# shieldMegaEstacionTT.net
KiCad netlist of a schematic drawn in Altium Designer
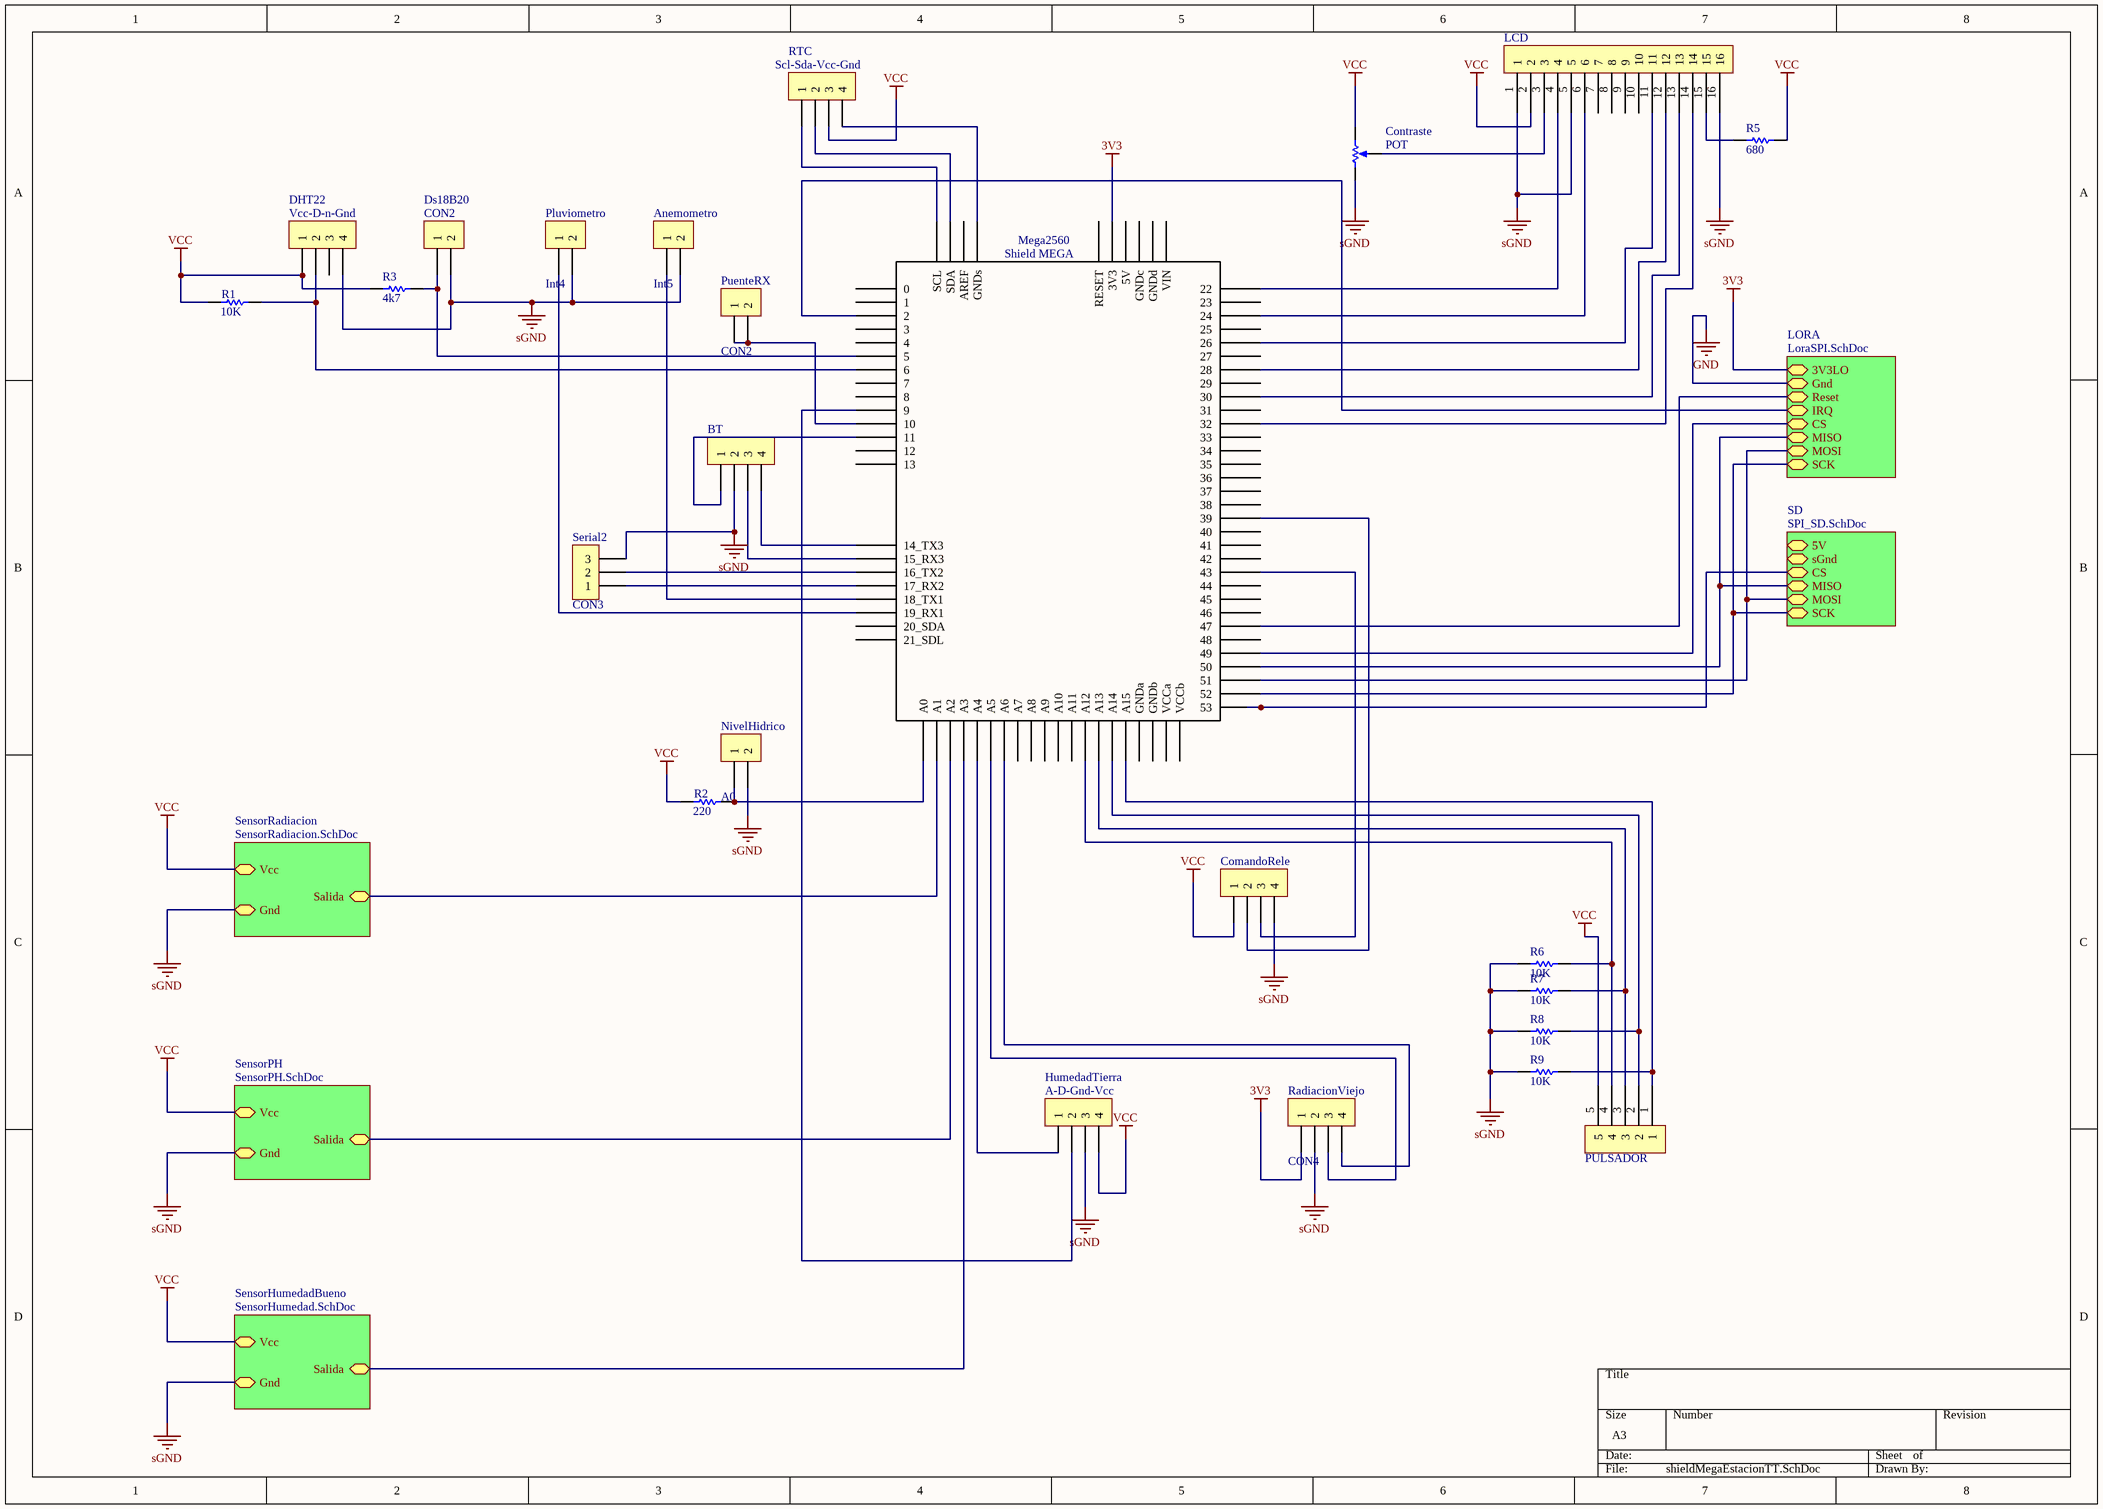
[diagram p0: shieldMegaEstacionTT.SchDoc]

(export (version "E")
  (design (tool "Eeschema 10.0.6"))
  (components
    (comp (ref "Anemometro")
      (value "Int5")
      (footprint "BORNERA2 - T")
      (description "Conector 2")
      (libsource (lib "IDTILab") (part "CON2"))
    )
    (comp (ref "BT")
      (value "CON4")
      (footprint "CON4")
      (description "Conector 4")
      (libsource (lib "DIE-SA Ingenieria") (part "CON4"))
    )
    (comp (ref "ComandoRele")
      (value "CON4")
      (footprint "CON4")
      (description "Conector 4")
      (libsource (lib "DIE-SA Ingenieria") (part "CON4"))
    )
    (comp (ref "Contraste")
      (value "POT")
      (footprint "PRESET2")
      (description "Potenciometro - Preset")
      (libsource (lib "DIE-SA Ingenieria") (part "POT"))
    )
    (comp (ref "DHT22")
      (value "Vcc-D-n-Gnd")
      (footprint "BORNERA4")
      (description "Conector 4")
      (libsource (lib "DIE-SA Ingenieria") (part "CON4"))
    )
    (comp (ref "Ds18B20")
      (value "CON2")
      (footprint "BORNERA2 - T")
      (description "Conector 2")
      (libsource (lib "IDTILab") (part "CON2"))
    )
    (comp (ref "HumedadTierra")
      (value "A-D-Gnd-Vcc")
      (footprint "CON4")
      (description "Conector 4")
      (libsource (lib "DIE-SA Ingenieria") (part "CON4"))
    )
    (comp (ref "LCD")
      (value "CON16")
      (footprint "CON2X8")
      (description "Conector 16")
      (libsource (lib "DIE-SA Ingenieria") (part "CON16"))
    )
    (comp (ref "Mega2560")
      (value "Shield MEGA")
      (footprint "Shield Mega")
      (libsource (lib "IDTILab") (part "Shield MEGA"))
    )
    (comp (ref "NivelHidrico")
      (value "A0")
      (footprint "BORNERA2 - T")
      (description "Conector 2")
      (libsource (lib "IDTILab") (part "CON2"))
    )
    (comp (ref "Pluviometro")
      (value "Int4")
      (footprint "BORNERA2 - T")
      (description "Conector 2")
      (libsource (lib "DIE-SA Ingenieria") (part "CON2"))
    )
    (comp (ref "PuenteRX")
      (value "CON2")
      (footprint "CON2")
      (description "Conector 2")
      (libsource (lib "IDTILab") (part "CON2"))
    )
    (comp (ref "PULSADOR")
      (value "CON5")
      (footprint "CON5")
      (description "Conector 5")
      (libsource (lib "DIE-SA Ingenieria") (part "CON5"))
    )
    (comp (ref "R1")
      (value "10K")
      (footprint "DIE-SA Ingenieria:RES300")
      (description "Resistencia")
      (libsource (lib "DIE-SA Ingenieria") (part "RES"))
    )
    (comp (ref "R2")
      (value "220")
      (footprint "DIE-SA Ingenieria:RES300")
      (description "Resistencia")
      (libsource (lib "DIE-SA Ingenieria") (part "RES"))
    )
    (comp (ref "R3")
      (value "4k7")
      (footprint "RES300")
      (description "Resistencia")
      (libsource (lib "DIE-SA Ingenieria") (part "RES"))
    )
    (comp (ref "R5")
      (value "680")
      (footprint "RES300")
      (description "Resistencia")
      (libsource (lib "DIE-SA Ingenieria") (part "RES"))
    )
    (comp (ref "R6")
      (value "10K")
      (footprint "RES300")
      (description "Resistencia")
      (libsource (lib "DIE-SA Ingenieria") (part "RES"))
    )
    (comp (ref "R7")
      (value "10K")
      (footprint "RES300")
      (description "Resistencia")
      (libsource (lib "DIE-SA Ingenieria") (part "RES"))
    )
    (comp (ref "R8")
      (value "10K")
      (footprint "RES300")
      (description "Resistencia")
      (libsource (lib "DIE-SA Ingenieria") (part "RES"))
    )
    (comp (ref "R9")
      (value "10K")
      (footprint "RES300")
      (description "Resistencia")
      (libsource (lib "DIE-SA Ingenieria") (part "RES"))
    )
    (comp (ref "RadiacionViejo")
      (value "CON4")
      (footprint "BORNERA4 - T")
      (description "Conector 4")
      (libsource (lib "DIE-SA Ingenieria") (part "CON4"))
    )
    (comp (ref "RTC")
      (value "Scl-Sda-Vcc-Gnd")
      (footprint "CON4")
      (description "Conector 4")
      (libsource (lib "DIE-SA Ingenieria") (part "CON4"))
    )
    (comp (ref "Serial2")
      (value "CON3")
      (footprint "CON3")
      (description "Conector 3")
      (libsource (lib "IDTILab") (part "CON3"))
    )
  )
  (nets
    (net (code "2") (name "/CS") (class "Default")
      (node (ref "Mega2560") (pin "49") (pinfunction "49_49") (pintype "passive"))
    )
    (net (code "3") (name "/CS_1") (class "Default")
      (node (ref "Mega2560") (pin "53") (pinfunction "53_53") (pintype "passive"))
    )
    (net (code "4") (name "/IRQ") (class "Default")
      (node (ref "Mega2560") (pin "2") (pinfunction "2_2") (pintype "passive"))
    )
    (net (code "5") (name "/MISO") (class "Default")
      (node (ref "Mega2560") (pin "50") (pinfunction "50_50") (pintype "passive"))
    )
    (net (code "6") (name "/MOSI") (class "Default")
      (node (ref "Mega2560") (pin "51") (pinfunction "51_51") (pintype "passive"))
    )
    (net (code "7") (name "/Reset") (class "Default")
      (node (ref "Mega2560") (pin "47") (pinfunction "47_47") (pintype "passive"))
    )
    (net (code "8") (name "/SCK") (class "Default")
      (node (ref "Mega2560") (pin "52") (pinfunction "52_52") (pintype "passive"))
    )
    (net (code "9") (name "/Salida") (class "Default")
      (node (ref "Mega2560") (pin "A3") (pinfunction "A3_A3") (pintype "passive"))
    )
    (net (code "10") (name "/Salida_1") (class "Default")
      (node (ref "Mega2560") (pin "A1") (pinfunction "A1_A1") (pintype "passive"))
    )
    (net (code "11") (name "/Salida_2") (class "Default")
      (node (ref "Mega2560") (pin "A2") (pinfunction "A2_A2") (pintype "passive"))
    )
    (net (code "13") (name "3V3") (class "Default")
      (node (ref "Mega2560") (pin "3V3") (pinfunction "3V3_3V3") (pintype "passive"))
      (node (ref "RadiacionViejo") (pin "1") (pinfunction "1_1") (pintype "passive"))
    )
    (net (code "15") (name "Net-(BT-Pad1)") (class "Default")
      (node (ref "BT") (pin "1") (pinfunction "1_1") (pintype "passive"))
      (node (ref "Mega2560") (pin "11") (pinfunction "11_11") (pintype "passive"))
    )
    (net (code "16") (name "Net-(ComandoRele-Pad2)") (class "Default")
      (node (ref "ComandoRele") (pin "2") (pinfunction "2_2") (pintype "passive"))
      (node (ref "Mega2560") (pin "39") (pinfunction "39_39") (pintype "passive"))
    )
    (net (code "17") (name "Net-(ComandoRele-Pad3)") (class "Default")
      (node (ref "ComandoRele") (pin "3") (pinfunction "3_3") (pintype "passive"))
      (node (ref "Mega2560") (pin "43") (pinfunction "43_43") (pintype "passive"))
    )
    (net (code "18") (name "Net-(Contraste-Pad3)") (class "Default")
      (node (ref "Contraste") (pin "3") (pinfunction "3_3") (pintype "passive"))
      (node (ref "LCD") (pin "3") (pinfunction "3_3") (pintype "passive"))
    )
    (net (code "19") (name "Net-(DHT22-Pad2)") (class "Default")
      (node (ref "DHT22") (pin "2") (pinfunction "2_2") (pintype "passive"))
      (node (ref "Mega2560") (pin "6") (pinfunction "6_6") (pintype "passive"))
      (node (ref "R1") (pin "2") (pinfunction "2_2") (pintype "passive"))
    )
    (net (code "20") (name "Net-(Ds18B20-Pad1)") (class "Default")
      (node (ref "Ds18B20") (pin "1") (pinfunction "1_1") (pintype "passive"))
      (node (ref "Mega2560") (pin "5") (pinfunction "5_5") (pintype "passive"))
      (node (ref "R3") (pin "2") (pinfunction "2_2") (pintype "passive"))
    )
    (net (code "21") (name "Net-(HumedadTierra-Pad1)") (class "Default")
      (node (ref "HumedadTierra") (pin "1") (pinfunction "1_1") (pintype "passive"))
      (node (ref "Mega2560") (pin "A4") (pinfunction "A4_A4") (pintype "passive"))
    )
    (net (code "22") (name "Net-(HumedadTierra-Pad2)") (class "Default")
      (node (ref "HumedadTierra") (pin "2") (pinfunction "2_2") (pintype "passive"))
      (node (ref "Mega2560") (pin "9") (pinfunction "9_9") (pintype "passive"))
    )
    (net (code "23") (name "Net-(LCD-Pad4)") (class "Default")
      (node (ref "LCD") (pin "4") (pinfunction "4_4") (pintype "passive"))
      (node (ref "Mega2560") (pin "22") (pinfunction "22_22") (pintype "passive"))
    )
    (net (code "24") (name "Net-(LCD-Pad6)") (class "Default")
      (node (ref "LCD") (pin "6") (pinfunction "6_6") (pintype "passive"))
      (node (ref "Mega2560") (pin "24") (pinfunction "24_24") (pintype "passive"))
    )
    (net (code "25") (name "Net-(LCD-Pad11)") (class "Default")
      (node (ref "LCD") (pin "11") (pinfunction "11_11") (pintype "passive"))
      (node (ref "Mega2560") (pin "26") (pinfunction "26_26") (pintype "passive"))
    )
    (net (code "26") (name "Net-(LCD-Pad12)") (class "Default")
      (node (ref "LCD") (pin "12") (pinfunction "12_12") (pintype "passive"))
      (node (ref "Mega2560") (pin "28") (pinfunction "28_28") (pintype "passive"))
    )
    (net (code "27") (name "Net-(LCD-Pad13)") (class "Default")
      (node (ref "LCD") (pin "13") (pinfunction "13_13") (pintype "passive"))
      (node (ref "Mega2560") (pin "30") (pinfunction "30_30") (pintype "passive"))
    )
    (net (code "28") (name "Net-(LCD-Pad14)") (class "Default")
      (node (ref "LCD") (pin "14") (pinfunction "14_14") (pintype "passive"))
      (node (ref "Mega2560") (pin "32") (pinfunction "32_32") (pintype "passive"))
    )
    (net (code "29") (name "Net-(LCD-Pad15)") (class "Default")
      (node (ref "LCD") (pin "15") (pinfunction "15_15") (pintype "passive"))
      (node (ref "R5") (pin "2") (pinfunction "2_2") (pintype "passive"))
    )
    (net (code "30") (name "Net-(Mega2560-14_TX3)") (class "Default")
      (node (ref "BT") (pin "4") (pinfunction "4_4") (pintype "passive"))
      (node (ref "Mega2560") (pin "14") (pinfunction "14_TX3_14") (pintype "passive"))
    )
    (net (code "31") (name "Net-(Mega2560-15_RX3)") (class "Default")
      (node (ref "BT") (pin "3") (pinfunction "3_3") (pintype "passive"))
      (node (ref "Mega2560") (pin "15") (pinfunction "15_RX3_15") (pintype "passive"))
    )
    (net (code "32") (name "Net-(Mega2560-16_TX2)") (class "Default")
      (node (ref "Mega2560") (pin "16") (pinfunction "16_TX2_16") (pintype "passive"))
      (node (ref "Serial2") (pin "2") (pinfunction "2_2") (pintype "passive"))
    )
    (net (code "33") (name "Net-(Mega2560-17_RX2)") (class "Default")
      (node (ref "Mega2560") (pin "17") (pinfunction "17_RX2_17") (pintype "passive"))
      (node (ref "Serial2") (pin "1") (pinfunction "1_1") (pintype "passive"))
    )
    (net (code "34") (name "Net-(Mega2560-18_TX1)") (class "Default")
      (node (ref "Anemometro") (pin "1") (pinfunction "1_1") (pintype "passive"))
      (node (ref "Mega2560") (pin "18") (pinfunction "18_TX1_18") (pintype "passive"))
    )
    (net (code "35") (name "Net-(Mega2560-19_RX1)") (class "Default")
      (node (ref "Mega2560") (pin "19") (pinfunction "19_RX1_19") (pintype "passive"))
      (node (ref "Pluviometro") (pin "1") (pinfunction "1_1") (pintype "passive"))
    )
    (net (code "36") (name "Net-(Mega2560-Pad10)") (class "Default")
      (node (ref "Mega2560") (pin "10") (pinfunction "10_10") (pintype "passive"))
      (node (ref "PuenteRX") (pin "1") (pinfunction "1_1") (pintype "passive"))
      (node (ref "PuenteRX") (pin "2") (pinfunction "2_2") (pintype "passive"))
    )
    (net (code "37") (name "Net-(Mega2560-PadA0)") (class "Default")
      (node (ref "Mega2560") (pin "A0") (pinfunction "A0_A0") (pintype "passive"))
      (node (ref "NivelHidrico") (pin "1") (pinfunction "1_1") (pintype "passive"))
      (node (ref "R2") (pin "2") (pinfunction "2_2") (pintype "passive"))
    )
    (net (code "38") (name "Net-(Mega2560-PadA5)") (class "Default")
      (node (ref "Mega2560") (pin "A5") (pinfunction "A5_A5") (pintype "passive"))
      (node (ref "RadiacionViejo") (pin "3") (pinfunction "3_3") (pintype "passive"))
    )
    (net (code "39") (name "Net-(Mega2560-PadA6)") (class "Default")
      (node (ref "Mega2560") (pin "A6") (pinfunction "A6_A6") (pintype "passive"))
      (node (ref "RadiacionViejo") (pin "4") (pinfunction "4_4") (pintype "passive"))
    )
    (net (code "40") (name "Net-(Mega2560-PadA12)") (class "Default")
      (node (ref "Mega2560") (pin "A12") (pinfunction "A12_A12") (pintype "passive"))
      (node (ref "PULSADOR") (pin "4") (pinfunction "4_4") (pintype "passive"))
      (node (ref "R6") (pin "2") (pinfunction "2_2") (pintype "passive"))
    )
    (net (code "41") (name "Net-(Mega2560-PadA13)") (class "Default")
      (node (ref "Mega2560") (pin "A13") (pinfunction "A13_A13") (pintype "passive"))
      (node (ref "PULSADOR") (pin "3") (pinfunction "3_3") (pintype "passive"))
      (node (ref "R7") (pin "2") (pinfunction "2_2") (pintype "passive"))
    )
    (net (code "42") (name "Net-(Mega2560-PadA14)") (class "Default")
      (node (ref "Mega2560") (pin "A14") (pinfunction "A14_A14") (pintype "passive"))
      (node (ref "PULSADOR") (pin "2") (pinfunction "2_2") (pintype "passive"))
      (node (ref "R8") (pin "2") (pinfunction "2_2") (pintype "passive"))
    )
    (net (code "43") (name "Net-(Mega2560-PadA15)") (class "Default")
      (node (ref "Mega2560") (pin "A15") (pinfunction "A15_A15") (pintype "passive"))
      (node (ref "PULSADOR") (pin "1") (pinfunction "1_1") (pintype "passive"))
      (node (ref "R9") (pin "2") (pinfunction "2_2") (pintype "passive"))
    )
    (net (code "44") (name "Net-(Mega2560-PadGNDs)") (class "Default")
      (node (ref "Mega2560") (pin "GNDs") (pinfunction "GNDs_GNDs") (pintype "passive"))
      (node (ref "RTC") (pin "4") (pinfunction "4_4") (pintype "passive"))
    )
    (net (code "45") (name "Net-(Mega2560-PadSCL)") (class "Default")
      (node (ref "Mega2560") (pin "SCL") (pinfunction "SCL_SCL") (pintype "passive"))
      (node (ref "RTC") (pin "1") (pinfunction "1_1") (pintype "passive"))
    )
    (net (code "46") (name "Net-(Mega2560-PadSDA)") (class "Default")
      (node (ref "Mega2560") (pin "SDA") (pinfunction "SDA_SDA") (pintype "passive"))
      (node (ref "RTC") (pin "2") (pinfunction "2_2") (pintype "passive"))
    )
    (net (code "47") (name "VCC") (class "Default")
      (node (ref "ComandoRele") (pin "1") (pinfunction "1_1") (pintype "passive"))
      (node (ref "Contraste") (pin "1") (pinfunction "1_1") (pintype "passive"))
      (node (ref "DHT22") (pin "1") (pinfunction "1_1") (pintype "passive"))
      (node (ref "HumedadTierra") (pin "4") (pinfunction "4_4") (pintype "passive"))
      (node (ref "LCD") (pin "2") (pinfunction "2_2") (pintype "passive"))
      (node (ref "PULSADOR") (pin "5") (pinfunction "5_5") (pintype "passive"))
      (node (ref "R1") (pin "1") (pinfunction "1_1") (pintype "passive"))
      (node (ref "R2") (pin "1") (pinfunction "1_1") (pintype "passive"))
      (node (ref "R3") (pin "1") (pinfunction "1_1") (pintype "passive"))
      (node (ref "R5") (pin "1") (pinfunction "1_1") (pintype "passive"))
      (node (ref "RTC") (pin "3") (pinfunction "3_3") (pintype "passive"))
    )
    (net (code "48") (name "sGND") (class "Default")
      (node (ref "Anemometro") (pin "2") (pinfunction "2_2") (pintype "passive"))
      (node (ref "BT") (pin "2") (pinfunction "2_2") (pintype "passive"))
      (node (ref "ComandoRele") (pin "4") (pinfunction "4_4") (pintype "passive"))
      (node (ref "Contraste") (pin "2") (pinfunction "2_2") (pintype "passive"))
      (node (ref "DHT22") (pin "4") (pinfunction "4_4") (pintype "passive"))
      (node (ref "Ds18B20") (pin "2") (pinfunction "2_2") (pintype "passive"))
      (node (ref "HumedadTierra") (pin "3") (pinfunction "3_3") (pintype "passive"))
      (node (ref "LCD") (pin "1") (pinfunction "1_1") (pintype "passive"))
      (node (ref "LCD") (pin "16") (pinfunction "16_16") (pintype "passive"))
      (node (ref "LCD") (pin "5") (pinfunction "5_5") (pintype "passive"))
      (node (ref "NivelHidrico") (pin "2") (pinfunction "2_2") (pintype "passive"))
      (node (ref "Pluviometro") (pin "2") (pinfunction "2_2") (pintype "passive"))
      (node (ref "R6") (pin "1") (pinfunction "1_1") (pintype "passive"))
      (node (ref "R7") (pin "1") (pinfunction "1_1") (pintype "passive"))
      (node (ref "R8") (pin "1") (pinfunction "1_1") (pintype "passive"))
      (node (ref "R9") (pin "1") (pinfunction "1_1") (pintype "passive"))
      (node (ref "RadiacionViejo") (pin "2") (pinfunction "2_2") (pintype "passive"))
      (node (ref "Serial2") (pin "3") (pinfunction "3_3") (pintype "passive"))
    )
    (net (code "49") (name "unconnected-(DHT22-Pad3)") (class "Default")
      (node (ref "DHT22") (pin "3") (pinfunction "3_3") (pintype "passive"))
    )
    (net (code "50") (name "unconnected-(LCD-Pad7)") (class "Default")
      (node (ref "LCD") (pin "7") (pinfunction "7_7") (pintype "passive"))
    )
    (net (code "51") (name "unconnected-(LCD-Pad8)") (class "Default")
      (node (ref "LCD") (pin "8") (pinfunction "8_8") (pintype "passive"))
    )
    (net (code "52") (name "unconnected-(LCD-Pad9)") (class "Default")
      (node (ref "LCD") (pin "9") (pinfunction "9_9") (pintype "passive"))
    )
    (net (code "53") (name "unconnected-(LCD-Pad10)") (class "Default")
      (node (ref "LCD") (pin "10") (pinfunction "10_10") (pintype "passive"))
    )
    (net (code "54") (name "unconnected-(Mega2560-20_SDA-Pad20)") (class "Default")
      (node (ref "Mega2560") (pin "20") (pinfunction "20_SDA_20") (pintype "passive"))
    )
    (net (code "55") (name "unconnected-(Mega2560-21_SDL-Pad21)") (class "Default")
      (node (ref "Mega2560") (pin "21") (pinfunction "21_SDL_21") (pintype "passive"))
    )
    (net (code "56") (name "unconnected-(Mega2560-Pad0)") (class "Default")
      (node (ref "Mega2560") (pin "0") (pinfunction "0_0") (pintype "passive"))
    )
    (net (code "57") (name "unconnected-(Mega2560-Pad1)") (class "Default")
      (node (ref "Mega2560") (pin "1") (pinfunction "1_1") (pintype "passive"))
    )
    (net (code "58") (name "unconnected-(Mega2560-Pad3)") (class "Default")
      (node (ref "Mega2560") (pin "3") (pinfunction "3_3") (pintype "passive"))
    )
    (net (code "59") (name "unconnected-(Mega2560-Pad4)") (class "Default")
      (node (ref "Mega2560") (pin "4") (pinfunction "4_4") (pintype "passive"))
    )
    (net (code "60") (name "unconnected-(Mega2560-Pad5V)") (class "Default")
      (node (ref "Mega2560") (pin "5V") (pinfunction "5V_5V") (pintype "passive"))
    )
    (net (code "61") (name "unconnected-(Mega2560-Pad7)") (class "Default")
      (node (ref "Mega2560") (pin "7") (pinfunction "7_7") (pintype "passive"))
    )
    (net (code "62") (name "unconnected-(Mega2560-Pad8)") (class "Default")
      (node (ref "Mega2560") (pin "8") (pinfunction "8_8") (pintype "passive"))
    )
    (net (code "63") (name "unconnected-(Mega2560-Pad12)") (class "Default")
      (node (ref "Mega2560") (pin "12") (pinfunction "12_12") (pintype "passive"))
    )
    (net (code "64") (name "unconnected-(Mega2560-Pad13)") (class "Default")
      (node (ref "Mega2560") (pin "13") (pinfunction "13_13") (pintype "passive"))
    )
    (net (code "65") (name "unconnected-(Mega2560-Pad23)") (class "Default")
      (node (ref "Mega2560") (pin "23") (pinfunction "23_23") (pintype "passive"))
    )
    (net (code "66") (name "unconnected-(Mega2560-Pad25)") (class "Default")
      (node (ref "Mega2560") (pin "25") (pinfunction "25_25") (pintype "passive"))
    )
    (net (code "67") (name "unconnected-(Mega2560-Pad27)") (class "Default")
      (node (ref "Mega2560") (pin "27") (pinfunction "27_27") (pintype "passive"))
    )
    (net (code "68") (name "unconnected-(Mega2560-Pad29)") (class "Default")
      (node (ref "Mega2560") (pin "29") (pinfunction "29_29") (pintype "passive"))
    )
    (net (code "69") (name "unconnected-(Mega2560-Pad31)") (class "Default")
      (node (ref "Mega2560") (pin "31") (pinfunction "31_31") (pintype "passive"))
    )
    (net (code "70") (name "unconnected-(Mega2560-Pad33)") (class "Default")
      (node (ref "Mega2560") (pin "33") (pinfunction "33_33") (pintype "passive"))
    )
    (net (code "71") (name "unconnected-(Mega2560-Pad34)") (class "Default")
      (node (ref "Mega2560") (pin "34") (pinfunction "34_34") (pintype "passive"))
    )
    (net (code "72") (name "unconnected-(Mega2560-Pad35)") (class "Default")
      (node (ref "Mega2560") (pin "35") (pinfunction "35_35") (pintype "passive"))
    )
    (net (code "73") (name "unconnected-(Mega2560-Pad36)") (class "Default")
      (node (ref "Mega2560") (pin "36") (pinfunction "36_36") (pintype "passive"))
    )
    (net (code "74") (name "unconnected-(Mega2560-Pad37)") (class "Default")
      (node (ref "Mega2560") (pin "37") (pinfunction "37_37") (pintype "passive"))
    )
    (net (code "75") (name "unconnected-(Mega2560-Pad38)") (class "Default")
      (node (ref "Mega2560") (pin "38") (pinfunction "38_38") (pintype "passive"))
    )
    (net (code "76") (name "unconnected-(Mega2560-Pad40)") (class "Default")
      (node (ref "Mega2560") (pin "40") (pinfunction "40_40") (pintype "passive"))
    )
    (net (code "77") (name "unconnected-(Mega2560-Pad41)") (class "Default")
      (node (ref "Mega2560") (pin "41") (pinfunction "41_41") (pintype "passive"))
    )
    (net (code "78") (name "unconnected-(Mega2560-Pad42)") (class "Default")
      (node (ref "Mega2560") (pin "42") (pinfunction "42_42") (pintype "passive"))
    )
    (net (code "79") (name "unconnected-(Mega2560-Pad44)") (class "Default")
      (node (ref "Mega2560") (pin "44") (pinfunction "44_44") (pintype "passive"))
    )
    (net (code "80") (name "unconnected-(Mega2560-Pad45)") (class "Default")
      (node (ref "Mega2560") (pin "45") (pinfunction "45_45") (pintype "passive"))
    )
    (net (code "81") (name "unconnected-(Mega2560-Pad46)") (class "Default")
      (node (ref "Mega2560") (pin "46") (pinfunction "46_46") (pintype "passive"))
    )
    (net (code "82") (name "unconnected-(Mega2560-Pad48)") (class "Default")
      (node (ref "Mega2560") (pin "48") (pinfunction "48_48") (pintype "passive"))
    )
    (net (code "83") (name "unconnected-(Mega2560-PadA7)") (class "Default")
      (node (ref "Mega2560") (pin "A7") (pinfunction "A7_A7") (pintype "passive"))
    )
    (net (code "84") (name "unconnected-(Mega2560-PadA8)") (class "Default")
      (node (ref "Mega2560") (pin "A8") (pinfunction "A8_A8") (pintype "passive"))
    )
    (net (code "85") (name "unconnected-(Mega2560-PadA9)") (class "Default")
      (node (ref "Mega2560") (pin "A9") (pinfunction "A9_A9") (pintype "passive"))
    )
    (net (code "86") (name "unconnected-(Mega2560-PadA10)") (class "Default")
      (node (ref "Mega2560") (pin "A10") (pinfunction "A10_A10") (pintype "passive"))
    )
    (net (code "87") (name "unconnected-(Mega2560-PadA11)") (class "Default")
      (node (ref "Mega2560") (pin "A11") (pinfunction "A11_A11") (pintype "passive"))
    )
    (net (code "88") (name "unconnected-(Mega2560-PadAREF)") (class "Default")
      (node (ref "Mega2560") (pin "AREF") (pinfunction "AREF_AREF") (pintype "passive"))
    )
    (net (code "89") (name "unconnected-(Mega2560-PadGNDa)") (class "Default")
      (node (ref "Mega2560") (pin "GNDa") (pinfunction "GNDa_GNDa") (pintype "passive"))
    )
    (net (code "90") (name "unconnected-(Mega2560-PadGNDb)") (class "Default")
      (node (ref "Mega2560") (pin "GNDb") (pinfunction "GNDb_GNDb") (pintype "passive"))
    )
    (net (code "91") (name "unconnected-(Mega2560-PadGNDc)") (class "Default")
      (node (ref "Mega2560") (pin "GNDc") (pinfunction "GNDc_GNDc") (pintype "passive"))
    )
    (net (code "92") (name "unconnected-(Mega2560-PadGNDd)") (class "Default")
      (node (ref "Mega2560") (pin "GNDd") (pinfunction "GNDd_GNDd") (pintype "passive"))
    )
    (net (code "93") (name "unconnected-(Mega2560-PadRESET)") (class "Default")
      (node (ref "Mega2560") (pin "RESET") (pinfunction "RESET_RESET") (pintype "passive"))
    )
    (net (code "94") (name "unconnected-(Mega2560-PadVCCa)") (class "Default")
      (node (ref "Mega2560") (pin "VCCa") (pinfunction "VCCa_VCCa") (pintype "passive"))
    )
    (net (code "95") (name "unconnected-(Mega2560-PadVCCb)") (class "Default")
      (node (ref "Mega2560") (pin "VCCb") (pinfunction "VCCb_VCCb") (pintype "passive"))
    )
    (net (code "96") (name "unconnected-(Mega2560-PadVIN)") (class "Default")
      (node (ref "Mega2560") (pin "VIN") (pinfunction "VIN_VIN") (pintype "passive"))
    )
  )
)
